# design.net
KiCad netlist of a schematic drawn in Altium Designer
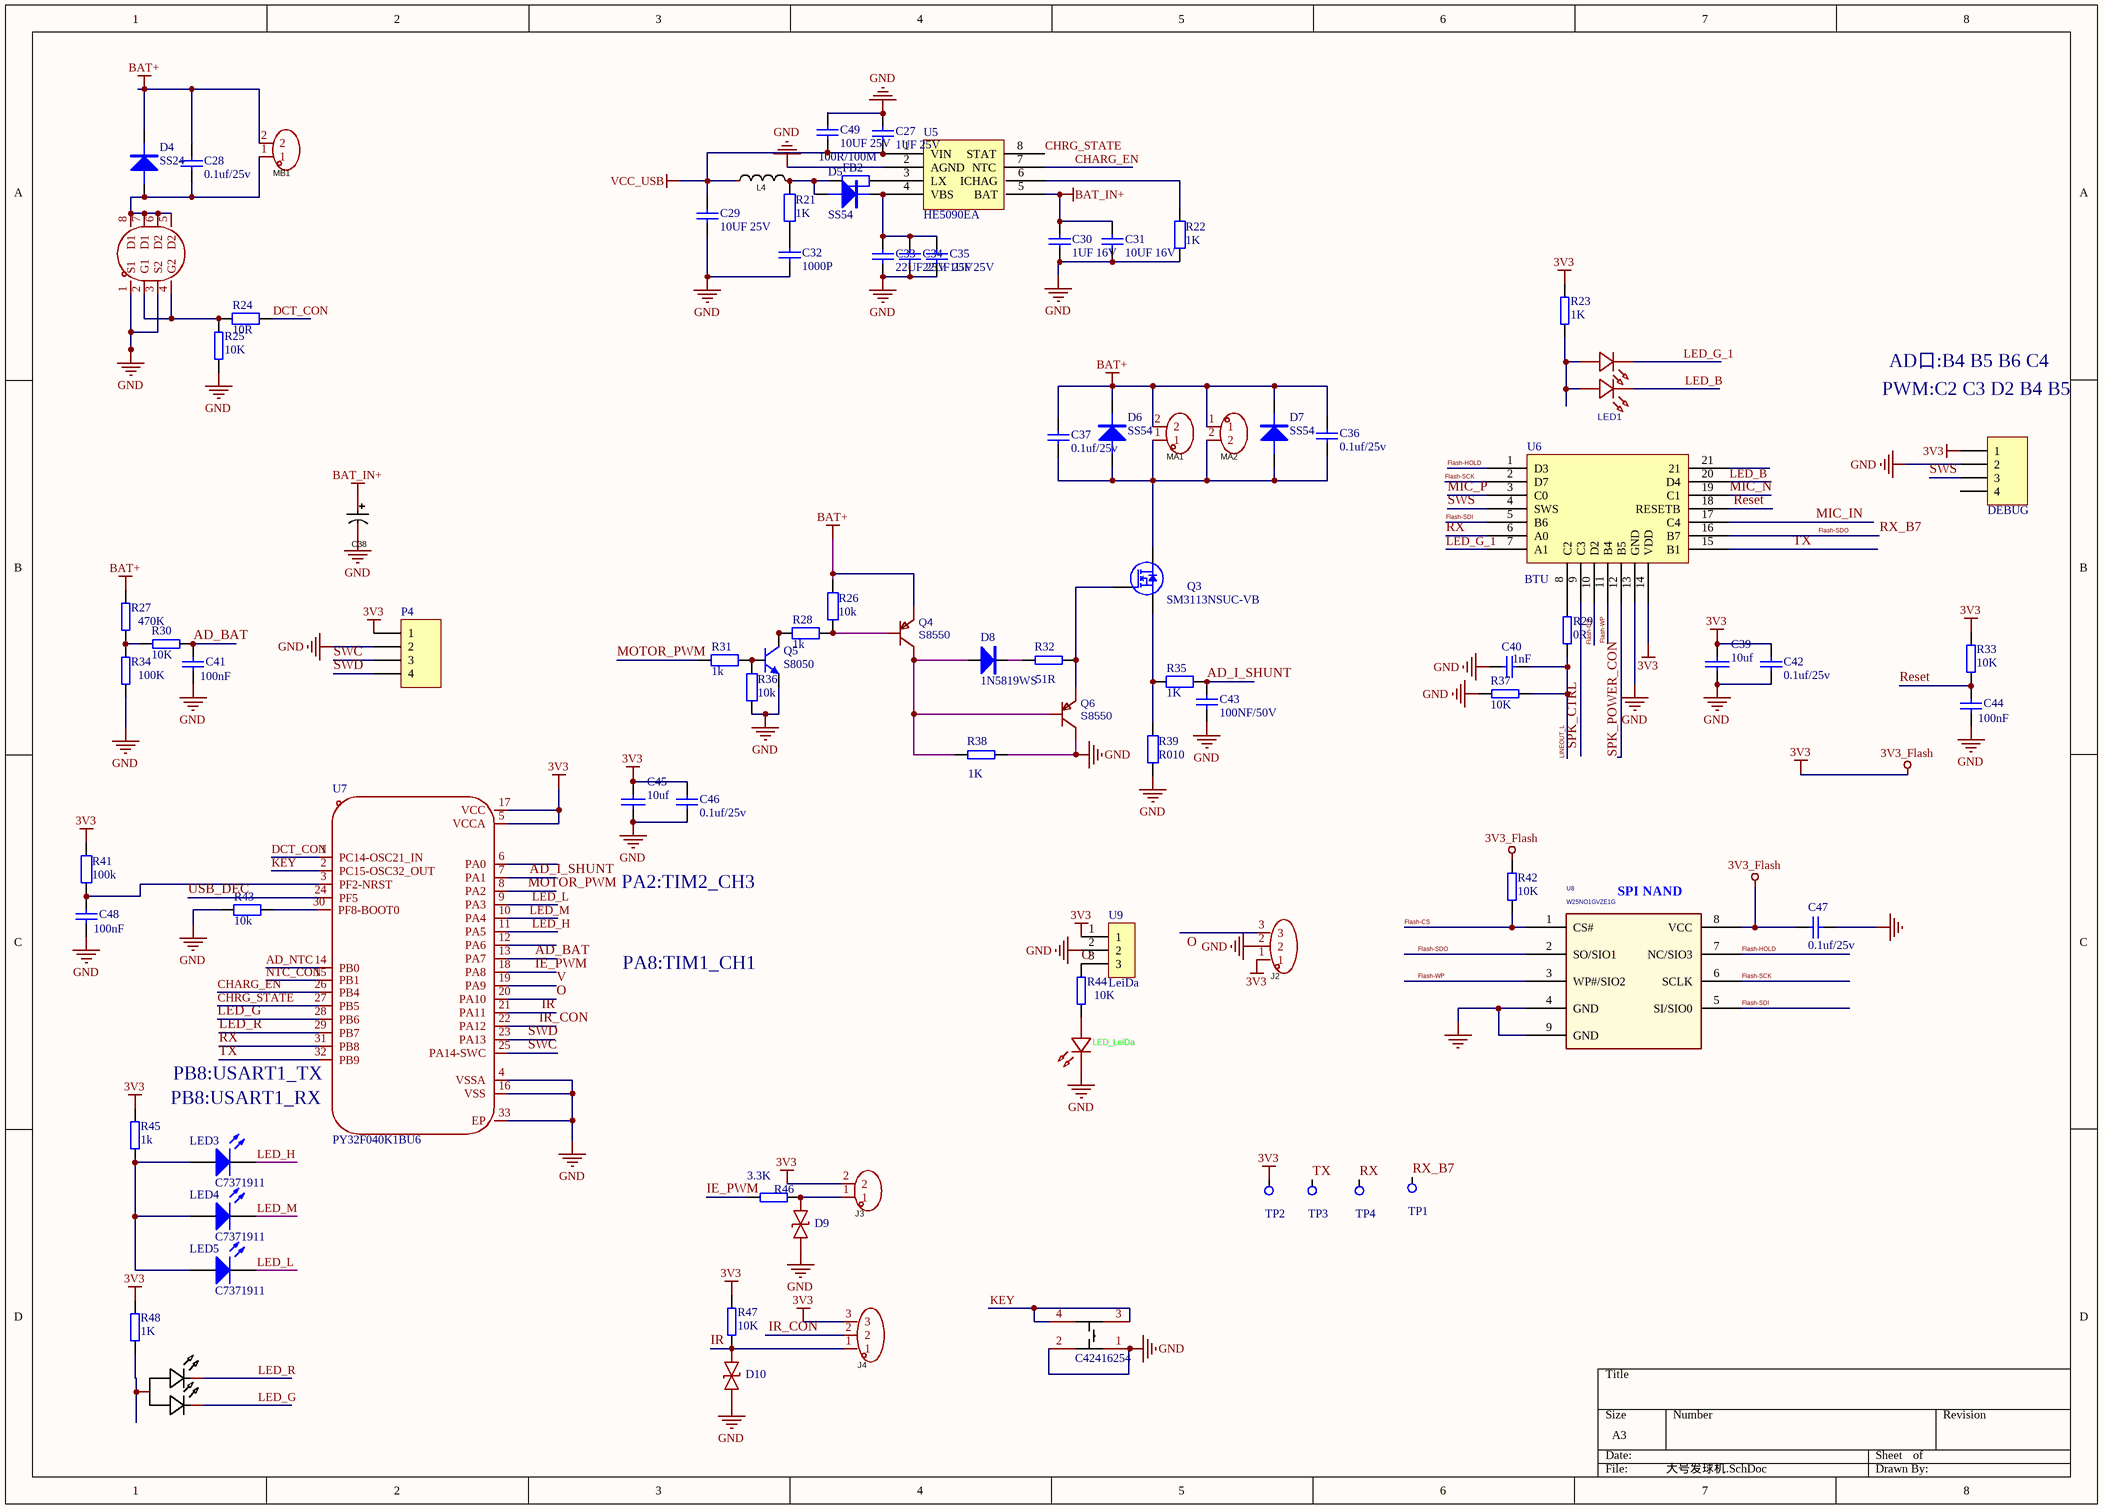
[diagram p0: 大号发球机.SchDoc]

(export (version "E")
  (design (tool "Eeschema 10.0.6"))
  (components
    (comp (ref "C27")
      (value "1UF 25V")
      (footprint "0603_C")
      (description "Capacitor")
      (fields (field (name "PUBLISHER") "Altium Limited"))
      (libsource (lib "*") (part "Cap"))
    )
    (comp (ref "C28")
      (value "0.1uf/25v")
      (footprint "0805_C")
      (description "Capacitor")
      (fields (field (name "PUBLISHER") "Altium Limited"))
      (libsource (lib "*") (part "Cap"))
    )
    (comp (ref "C29") (value "10UF 25V") (footprint "0603_c") (libsource (lib "DIY") (part "CAP")))
    (comp (ref "C30")
      (value "1UF 16V")
      (footprint "0603_C")
      (description "Capacitor")
      (fields (field (name "PUBLISHER") "Altium Limited"))
      (libsource (lib "*") (part "Cap"))
    )
    (comp (ref "C31") (value "10UF 16V") (footprint "0603_c") (libsource (lib "DIY") (part "CAP")))
    (comp (ref "C32")
      (value "1000P")
      (footprint "0603_C")
      (description "Capacitor")
      (fields (field (name "PUBLISHER") "Altium Limited"))
      (libsource (lib "*") (part "Cap"))
    )
    (comp (ref "C33") (value "22UF 25V") (footprint "0805_C") (libsource (lib "DIY") (part "CAP")))
    (comp (ref "C34") (value "22UF 25V") (footprint "0805_C") (libsource (lib "DIY") (part "CAP")))
    (comp (ref "C35")
      (value "1UF 25V")
      (footprint "0603_C")
      (description "Capacitor")
      (fields (field (name "PUBLISHER") "Altium Limited"))
      (libsource (lib "*") (part "Cap"))
    )
    (comp (ref "C36")
      (value "0.1uf/25v")
      (footprint "0805_C")
      (description "Capacitor")
      (fields (field (name "PUBLISHER") "Altium Limited"))
      (libsource (lib "*") (part "Cap"))
    )
    (comp (ref "C37")
      (value "0.1uf/25v")
      (footprint "0805_C")
      (description "Capacitor")
      (fields (field (name "PUBLISHER") "Altium Limited"))
      (libsource (lib "*") (part "Cap"))
    )
    (comp (ref "C38")
      (value "220uf/25v")
      (footprint "SMD 6.3*7.7")
      (fields (field (name "MANUFACTURER PART") "RVT1A221M0605"))
      (libsource (lib "altium-import") (part "root_0_RVT1A221M0605_C72494_"))
    )
    (comp (ref "C39")
      (value "10uf")
      (footprint "0603_c")
      (description "C-?-K-0603")
      (libsource (lib "HJ_AD_SchLib") (part "C-0603"))
    )
    (comp (ref "C40") (value "1nF") (footprint "0603_C") (libsource (lib "DIY") (part "CAP")))
    (comp (ref "C41") (value "100nF") (footprint "0603_C") (libsource (lib "DIY") (part "CAP")))
    (comp (ref "C42")
      (value "0.1uf/25v")
      (footprint "0603_C")
      (description "Capacitor")
      (fields (field (name "PUBLISHER") "Altium Limited"))
      (libsource (lib "*") (part "Cap"))
    )
    (comp (ref "C43")
      (value "100NF/50V")
      (footprint "0603_C")
      (description "无极电容")
      (libsource (lib "电容电阻电感保险") (part "Cap1"))
    )
    (comp (ref "C44") (value "100nF") (footprint "0603_C") (libsource (lib "DIY") (part "CAP")))
    (comp (ref "C45")
      (value "10uf")
      (footprint "0603_c")
      (description "C-?-K-0603")
      (libsource (lib "HJ_AD_SchLib") (part "C-0603"))
    )
    (comp (ref "C46")
      (value "0.1uf/25v")
      (footprint "0603_C")
      (description "Capacitor")
      (fields (field (name "PUBLISHER") "Altium Limited"))
      (libsource (lib "*") (part "Cap"))
    )
    (comp (ref "C47")
      (value "0.1uf/25v")
      (footprint "0603_C")
      (description "Capacitor")
      (fields (field (name "PUBLISHER") "Altium Limited"))
      (libsource (lib "*") (part "Cap"))
    )
    (comp (ref "C48") (value "100nF") (footprint "0603_C") (libsource (lib "DIY") (part "CAP")))
    (comp (ref "C49") (value "10UF 25V") (footprint "0603_c") (libsource (lib "DIY") (part "CAP")))
    (comp (ref "D4")
      (value "SS24")
      (footprint "SMA")
      (description "DO214AC")
      (libsource (lib "RONCO_SchLib") (part "D-SS24-SMA"))
    )
    (comp (ref "D5")
      (value "SS54")
      (footprint "SMA")
      (description "DO214AC")
      (libsource (lib "RONCO_SchLib") (part "D-SS24-SMA"))
    )
    (comp (ref "D6")
      (value "SS54")
      (footprint "SMA")
      (description "DO214AC")
      (libsource (lib "RONCO_SchLib") (part "D-SS24-SMA"))
    )
    (comp (ref "D7")
      (value "SS54")
      (footprint "SMA")
      (description "DO214AC")
      (libsource (lib "RONCO_SchLib") (part "D-SS24-SMA"))
    )
    (comp (ref "D8") (value "1N5819WS") (footprint "SOD-323") (libsource (lib "DIY") (part "DIODE")))
    (comp (ref "D9")
      (value "LESD5Z5.0CT1G")
      (footprint "SOD-523_L1.2-W0.8-LS1.6-RD")
      (libsource (lib "altium-import") (part "root_1_LESD5Z5.0CT1G_"))
    )
    (comp (ref "D10")
      (value "LESD5Z5.0CT1G")
      (footprint "SOD-523_L1.2-W0.8-LS1.6-RD")
      (libsource (lib "altium-import") (part "root_1_LESD5Z5.0CT1G_"))
    )
    (comp (ref "FB2")
      (value "100R/100M")
      (footprint "0805_R")
      (description "Resistor")
      (fields (field (name "PUBLISHER") "Altium Limited"))
      (libsource (lib "") (part "Res2_1"))
    )
    (comp (ref "J2")
      (value "2.0-3P LT")
      (footprint "CONN-SMD_2.0-3PLT")
      (fields (field (name "MANUFACTURER PART") "BX-PH2.0-3PZZ"))
      (libsource (lib "altium-import") (part "root_2_mirrored_BX-PH2.0-3PZZ_"))
    )
    (comp (ref "J3")
      (value "2.54-2P LT")
      (footprint "CONN-SMD_2.54-2PLT")
      (fields (field (name "MANUFACTURER PART") "BX-PH2.0-2PZZ"))
      (libsource (lib "altium-import") (part "root_2_mirrored_BX-PH2.0-2PZZ_"))
    )
    (comp (ref "J4")
      (value "2.54-3P LT")
      (footprint "CONN-SMD_2.54-3P-LT")
      (fields (field (name "MANUFACTURER PART") "BX-PH2.0-3PZZ"))
      (libsource (lib "altium-import") (part "root_2_mirrored_BX-PH2.0-3PZZ_"))
    )
    (comp (ref "K1")
      (value "C42416254")
      (footprint "KEY_SMD_4P")
      (fields (field (name "MANUFACTURER PART") "TS-1002S-05026C"))
      (libsource (lib "altium-import") (part "root_2_TS-1002S-05026C_"))
    )
    (comp (ref "L4")
      (value "0630-2R2")
      (footprint "L 6.6*7.0")
      (fields (field (name "MANUFACTURER PART") "FXL0630-4R7-M"))
      (libsource (lib "altium-import") (part "root_0_FXL0630-4R7-M_"))
    )
    (comp (ref "LED1")
      (value "bl-hb5gk33b-trb")
      (footprint "LED-SMD_4P-L3.2-W2.7-P1.40-TL_BL-HB5GK33B-TRB")
      (fields (field (name "MANUFACTURERPART") "BL-HB5GK33B-TRB"))
      (libsource (lib "altium-import") (part "root_2_bl-hb5gk33b-trb_"))
    )
    (comp (ref "LED2")
      (value "LED_LeiDa")
      (footprint "0805_LED")
      (fields (field (name "MANUFACTURER PART") "XL-2012SURC"))
      (libsource (lib "altium-import") (part "root_1_XL-2012SURC_"))
    )
    (comp (ref "LED3")
      (value "C7371911")
      (footprint "0805_LED")
      (description "Typical INFRARED GaAs LED")
      (fields (field (name "PUBLISHER") "Altium Limited"))
      (libsource (lib "Miscellaneous Devices") (part "LED0"))
    )
    (comp (ref "LED4")
      (value "C7371911")
      (footprint "0805_LED")
      (description "Typical INFRARED GaAs LED")
      (fields (field (name "PUBLISHER") "Altium Limited"))
      (libsource (lib "Miscellaneous Devices") (part "LED0"))
    )
    (comp (ref "LED5")
      (value "C7371911")
      (footprint "0805_LED")
      (description "Typical INFRARED GaAs LED")
      (fields (field (name "PUBLISHER") "Altium Limited"))
      (libsource (lib "Miscellaneous Devices") (part "LED0"))
    )
    (comp (ref "LED6")
      (value "C5221230")
      (footprint "LED-SMD_4P-L3.2-W1.6-TL_XL-3216SURUGC")
      (fields (field (name "MANUFACTURER PART") "TZ-LAMP03RG4HD-A"))
      (libsource (lib "altium-import") (part "root_0_TZ-LAMP03RG4HD-A_"))
    )
    (comp (ref "MA1")
      (value "2.54-2P LT")
      (footprint "CONN-SMD_2.54-2PLT")
      (fields (field (name "MANUFACTURER PART") "BX-PH2.0-2PZZ"))
      (libsource (lib "altium-import") (part "root_2_mirrored_BX-PH2.0-2PZZ_"))
    )
    (comp (ref "MA2")
      (value "2.54-2P LT")
      (footprint "CONN-SMD_2.54-2PLT")
      (fields (field (name "MANUFACTURER PART") "BX-PH2.0-2PZZ"))
      (libsource (lib "altium-import") (part "root_0_BX-PH2.0-2PZZ_"))
    )
    (comp (ref "MB1")
      (value "2.54-2P LT")
      (footprint "CONN-SMD_2.54-2PLT")
      (fields (field (name "MANUFACTURER PART") "BX-PH2.0-2PZZ"))
      (libsource (lib "altium-import") (part "root_2_mirrored_BX-PH2.0-2PZZ_"))
    )
    (comp (ref "P3")
      (value "DEBUG")
      (footprint "SIP4-2.54")
      (description "Header, 4-Pin")
      (fields (field (name "PUBLISHER") "Altium Limited"))
      (libsource (lib "Miscellaneous Connectors") (part "Header 4"))
    )
    (comp (ref "P4")
      (value "~")
      (footprint "4P 2.0")
      (description "Header, 4-Pin")
      (fields (field (name "PUBLISHER") "Altium Limited"))
      (libsource (lib "Miscellaneous Connectors") (part "Header 4"))
    )
    (comp (ref "Q2")
      (value "AP9926")
      (footprint "SOP8")
      (fields (field (name "MANUFACTURER") "WINSOK(微硕)") (field (name "MANUFACTURER PART") "WSP9936"))
      (libsource (lib "altium-import") (part "root_1_WSP9936_"))
    )
    (comp (ref "Q3")
      (value "SM3113NSUC-VB")
      (footprint "TO-252")
      (description "N沟道MOS管")
      (libsource (lib "二三极管mos可控硅") (part "NMOS1"))
    )
    (comp (ref "Q4")
      (value "S8550")
      (footprint "SOT-23")
      (fields (field (name "BOM_SUPPLIER PART") "C545533") (field (name "CONTRIBUTOR") "LCSC"))
      (libsource (lib "altium-import") (part "root_2_mirrored_S8550_C545533_"))
    )
    (comp (ref "Q5")
      (value "S8050")
      (footprint "SOT-23(SOT-23-3)")
      (description "NPN三极管")
      (libsource (lib "二三极管mos可控硅") (part "NPN_sot23"))
    )
    (comp (ref "Q6")
      (value "S8550")
      (footprint "SOT-23")
      (fields (field (name "BOM_SUPPLIER PART") "C545533") (field (name "CONTRIBUTOR") "LCSC"))
      (libsource (lib "altium-import") (part "root_2_mirrored_S8550_C545533_"))
    )
    (comp (ref "R21")
      (value "1K")
      (footprint "0603_R")
      (description "Resistor")
      (fields (field (name "PUBLISHER") "Altium Limited"))
      (libsource (lib "") (part "Res2_2"))
    )
    (comp (ref "R22")
      (value "1K")
      (footprint "0603_R")
      (description "Resistor")
      (fields (field (name "PUBLISHER") "Altium Limited"))
      (libsource (lib "") (part "Res2_2"))
    )
    (comp (ref "R23") (value "1K") (footprint "0603_R") (libsource (lib "DIY") (part "RES")))
    (comp (ref "R24")
      (value "10R")
      (footprint "0603_R")
      (description "Resistor")
      (fields (field (name "PUBLISHER") "Altium Limited"))
      (libsource (lib "") (part "Res2_1"))
    )
    (comp (ref "R25") (value "10K") (footprint "0603_R") (libsource (lib "DIY") (part "RES")))
    (comp (ref "R26")
      (value "10k")
      (footprint "0603_R")
      (description "Resistor")
      (fields (field (name "PUBLISHER") "Altium Limited"))
      (libsource (lib "*") (part "Res2"))
    )
    (comp (ref "R27") (value "470K") (footprint "0603_R") (libsource (lib "DIY") (part "RES")))
    (comp (ref "R28")
      (value "1k")
      (footprint "0603_R")
      (description "Resistor")
      (fields (field (name "PUBLISHER") "Altium Limited"))
      (libsource (lib "") (part "Res2_3"))
    )
    (comp (ref "R29") (value "0R") (footprint "0603_R") (libsource (lib "DIY") (part "RES")))
    (comp (ref "R30") (value "10K") (footprint "0603_R") (libsource (lib "DIY") (part "RES")))
    (comp (ref "R31")
      (value "1k")
      (footprint "0603_R")
      (description "Resistor")
      (fields (field (name "PUBLISHER") "Altium Limited"))
      (libsource (lib "") (part "Res2_3"))
    )
    (comp (ref "R32") (value "51R") (footprint "0603_R") (libsource (lib "*") (part "RES")))
    (comp (ref "R33") (value "10K") (footprint "0603_R") (libsource (lib "DIY") (part "RES")))
    (comp (ref "R34") (value "100K") (footprint "0603_R") (libsource (lib "DIY") (part "RES")))
    (comp (ref "R35")
      (value "1K")
      (footprint "0603_R")
      (description "Resistor")
      (fields (field (name "PUBLISHER") "Altium Limited"))
      (libsource (lib "") (part "Res2_1"))
    )
    (comp (ref "R36")
      (value "10k")
      (footprint "0603_R")
      (description "Resistor")
      (fields (field (name "PUBLISHER") "Altium Limited"))
      (libsource (lib "*") (part "Res2"))
    )
    (comp (ref "R37") (value "10K") (footprint "0603_R") (libsource (lib "DIY") (part "RES")))
    (comp (ref "R38") (value "1K") (footprint "0603_R") (libsource (lib "*") (part "RES")))
    (comp (ref "R39")
      (value "R010")
      (footprint "2512_R")
      (description "Resistor")
      (fields (field (name "PUBLISHER") "Altium Limited"))
      (libsource (lib "*") (part "Res2"))
    )
    (comp (ref "R41")
      (value "100k")
      (footprint "0603_R")
      (description "Resistor")
      (fields (field (name "PUBLISHER") "Altium Limited"))
      (libsource (lib "") (part "Res2_2"))
    )
    (comp (ref "R42") (value "10K") (footprint "0603_R") (libsource (lib "DIY") (part "RES")))
    (comp (ref "R43")
      (value "10k")
      (footprint "0603_R")
      (description "Resistor")
      (fields (field (name "PUBLISHER") "Altium Limited"))
      (libsource (lib "") (part "Res2_1"))
    )
    (comp (ref "R44") (value "10K") (footprint "0603_R") (libsource (lib "DIY") (part "RES")))
    (comp (ref "R45") (value "1k") (footprint "0603_r") (libsource (lib "DIY") (part "RES")))
    (comp (ref "R46") (value "3.3K") (footprint "0603_R") (libsource (lib "DIY") (part "RES")))
    (comp (ref "R47") (value "10K") (footprint "0603_R") (libsource (lib "DIY") (part "RES")))
    (comp (ref "R48") (value "1K") (footprint "0603_R") (libsource (lib "DIY") (part "RES")))
    (comp (ref "TP1") (value "~") (footprint "TP") (libsource (lib "LZJ自用") (part "J-CSD")))
    (comp (ref "TP2") (value "~") (footprint "TP") (libsource (lib "LZJ自用") (part "J-CSD")))
    (comp (ref "TP3") (value "~") (footprint "TP") (libsource (lib "LZJ自用") (part "J-CSD")))
    (comp (ref "TP4") (value "~") (footprint "TP") (libsource (lib "LZJ自用") (part "J-CSD")))
    (comp (ref "U5") (value "HE5090EA") (footprint "SOP8-9") (libsource (lib "MyLib") (part "HE5090EA")))
    (comp (ref "U6") (value "BTU") (footprint "BTU") (libsource (lib "MyLib") (part "BTU")))
    (comp (ref "U7")
      (value "PY32F040K1BU6")
      (footprint "QFN-32_L5.0-W5.0-P0.50-BL-EP3.4")
      (libsource (lib "MyLib") (part "PY32F040K1BU6"))
    )
    (comp (ref "U8") (value "W25NO1GVZE1G") (footprint "SOP8-150+208") (libsource (lib "*") (part "24C08_3")))
    (comp (ref "U9") (value "LeiDa") (footprint "5.8G") (libsource (lib "MyLib") (part "CON3")))
  )
  (nets
    (net (code "1") (name "/AD_BAT") (class "Default")
      (node (ref "C41") (pin "2") (pintype "passive"))
      (node (ref "R30") (pin "2") (pinfunction "2_2") (pintype "passive"))
      (node (ref "U7") (pin "13") (pinfunction "PA7_13") (pintype "passive"))
    )
    (net (code "2") (name "/AD_I_SHUNT") (class "Default")
      (node (ref "C43") (pin "1") (pinfunction "1_1") (pintype "passive"))
      (node (ref "R35") (pin "1") (pinfunction "1_1") (pintype "passive"))
      (node (ref "U7") (pin "7") (pinfunction "PA1_7") (pintype "passive"))
    )
    (net (code "3") (name "/AD_NTC") (class "Default")
      (node (ref "U7") (pin "14") (pinfunction "PB0_14") (pintype "passive"))
    )
    (net (code "4") (name "/CHARG_EN") (class "Default")
      (node (ref "U5") (pin "7") (pinfunction "NTC_7") (pintype "passive"))
      (node (ref "U7") (pin "26") (pinfunction "PB4_26") (pintype "passive"))
    )
    (net (code "5") (name "/CHRG_STATE") (class "Default")
      (node (ref "U5") (pin "8") (pinfunction "STAT_8") (pintype "passive"))
      (node (ref "U7") (pin "27") (pinfunction "PB5_27") (pintype "passive"))
    )
    (net (code "6") (name "/DCT_CON") (class "Default")
      (node (ref "R24") (pin "1") (pinfunction "1_1") (pintype "passive"))
      (node (ref "U7") (pin "1") (pinfunction "PC14-OSC21_IN_1") (pintype "passive"))
    )
    (net (code "7") (name "/Flash-CS") (class "Default")
      (node (ref "R42") (pin "1") (pinfunction "1_1") (pintype "passive"))
      (node (ref "U6") (pin "10") (pinfunction "D2_10") (pintype "passive"))
      (node (ref "U8") (pin "1") (pinfunction "CS#_1") (pintype "passive"))
    )
    (net (code "8") (name "/Flash-HOLD") (class "Default")
      (node (ref "U6") (pin "1") (pinfunction "D3_1") (pintype "passive"))
      (node (ref "U8") (pin "7") (pinfunction "NC/SIO3_7") (pintype "passive"))
    )
    (net (code "9") (name "/Flash-SCK") (class "Default")
      (node (ref "U6") (pin "2") (pinfunction "D7_2") (pintype "passive"))
      (node (ref "U8") (pin "6") (pinfunction "SCLK_6") (pintype "passive"))
    )
    (net (code "10") (name "/Flash-SDI") (class "Default")
      (node (ref "U6") (pin "5") (pinfunction "B6_5") (pintype "passive"))
      (node (ref "U8") (pin "5") (pinfunction "SI/SIO0_5") (pintype "passive"))
    )
    (net (code "11") (name "/Flash-SDO") (class "Default")
      (node (ref "TP1") (pin "1") (pinfunction "1_1") (pintype "passive"))
      (node (ref "U6") (pin "16") (pinfunction "B7_16") (pintype "passive"))
      (node (ref "U8") (pin "2") (pinfunction "SO/SIO1_2") (pintype "passive"))
    )
    (net (code "12") (name "/Flash-WP") (class "Default")
      (node (ref "U6") (pin "11") (pinfunction "B4_11") (pintype "passive"))
      (node (ref "U8") (pin "3") (pinfunction "WP#/SIO2_3") (pintype "passive"))
    )
    (net (code "13") (name "/IE_PWM") (class "Default")
      (node (ref "R46") (pin "1") (pinfunction "1_1") (pintype "passive"))
      (node (ref "U7") (pin "18") (pinfunction "PA8_18") (pintype "passive"))
    )
    (net (code "14") (name "/IR") (class "Default")
      (node (ref "D10") (pin "2") (pinfunction "2_2") (pintype "passive"))
      (node (ref "J4") (pin "1") (pinfunction "1_1") (pintype "passive"))
      (node (ref "R47") (pin "1") (pinfunction "1_1") (pintype "passive"))
      (node (ref "U7") (pin "21") (pinfunction "PA11_21") (pintype "passive"))
    )
    (net (code "15") (name "/IR_CON") (class "Default")
      (node (ref "J4") (pin "2") (pinfunction "2_2") (pintype "passive"))
      (node (ref "U7") (pin "22") (pinfunction "PA12_22") (pintype "passive"))
    )
    (net (code "16") (name "/KEY") (class "Default")
      (node (ref "K1") (pin "3") (pinfunction "3_3") (pintype "passive"))
      (node (ref "K1") (pin "4") (pinfunction "4_4") (pintype "passive"))
      (node (ref "U7") (pin "2") (pinfunction "PC15-OSC32_OUT_2") (pintype "passive"))
    )
    (net (code "17") (name "/LED_B") (class "Default")
      (node (ref "LED1") (pin "1") (pinfunction "C_1") (pintype "passive"))
      (node (ref "U6") (pin "20") (pinfunction "D4_20") (pintype "passive"))
    )
    (net (code "18") (name "/LED_G") (class "Default")
      (node (ref "LED6") (pin "3") (pinfunction "-_3") (pintype "passive"))
      (node (ref "U7") (pin "28") (pinfunction "PB6_28") (pintype "passive"))
    )
    (net (code "19") (name "/LED_G_1") (class "Default")
      (node (ref "LED1") (pin "2") (pinfunction "C_2") (pintype "passive"))
      (node (ref "U6") (pin "7") (pinfunction "A1_7") (pintype "passive"))
    )
    (net (code "20") (name "/LED_H") (class "Default")
      (node (ref "LED3") (pin "2") (pinfunction "K_2") (pintype "passive"))
      (node (ref "U7") (pin "11") (pinfunction "PA5_11") (pintype "passive"))
    )
    (net (code "21") (name "/LED_L") (class "Default")
      (node (ref "LED5") (pin "2") (pinfunction "K_2") (pintype "passive"))
      (node (ref "U7") (pin "9") (pinfunction "PA3_9") (pintype "passive"))
    )
    (net (code "22") (name "/LED_M") (class "Default")
      (node (ref "LED4") (pin "2") (pinfunction "K_2") (pintype "passive"))
      (node (ref "U7") (pin "10") (pinfunction "PA4_10") (pintype "passive"))
    )
    (net (code "23") (name "/LED_R") (class "Default")
      (node (ref "LED6") (pin "1") (pinfunction "-_1") (pintype "passive"))
      (node (ref "U7") (pin "29") (pinfunction "PB7_29") (pintype "passive"))
    )
    (net (code "24") (name "/LINEOUT_L") (class "Default")
      (node (ref "C40") (pin "1") (pintype "passive"))
      (node (ref "R29") (pin "1") (pinfunction "1_1") (pintype "passive"))
      (node (ref "R37") (pin "2") (pinfunction "2_2") (pintype "passive"))
    )
    (net (code "25") (name "/MIC_IN") (class "Default")
      (node (ref "U6") (pin "17") (pinfunction "C4_17") (pintype "passive"))
    )
    (net (code "26") (name "/MIC_N") (class "Default")
      (node (ref "U6") (pin "19") (pinfunction "C1_19") (pintype "passive"))
    )
    (net (code "27") (name "/MIC_P") (class "Default")
      (node (ref "U6") (pin "3") (pinfunction "C0_3") (pintype "passive"))
    )
    (net (code "28") (name "/MOTOR_PWM") (class "Default")
      (node (ref "R31") (pin "1") (pinfunction "1_1") (pintype "passive"))
      (node (ref "U7") (pin "8") (pinfunction "PA2_8") (pintype "passive"))
    )
    (net (code "29") (name "/NTC_CON") (class "Default")
      (node (ref "U7") (pin "15") (pinfunction "PB1_15") (pintype "passive"))
    )
    (net (code "30") (name "/O") (class "Default")
      (node (ref "J2") (pin "3") (pinfunction "3_3") (pintype "passive"))
      (node (ref "R44") (pin "1") (pinfunction "1_1") (pintype "passive"))
      (node (ref "U7") (pin "20") (pinfunction "PA10_20") (pintype "passive"))
      (node (ref "U9") (pin "3") (pinfunction "3_3") (pintype "passive"))
    )
    (net (code "31") (name "/RX") (class "Default")
      (node (ref "TP4") (pin "1") (pinfunction "1_1") (pintype "passive"))
      (node (ref "U6") (pin "6") (pinfunction "A0_6") (pintype "passive"))
      (node (ref "U7") (pin "31") (pinfunction "PB8_31") (pintype "passive"))
    )
    (net (code "32") (name "/Reset") (class "Default")
      (node (ref "C44") (pin "2") (pintype "passive"))
      (node (ref "R33") (pin "2") (pinfunction "2_2") (pintype "passive"))
      (node (ref "U6") (pin "18") (pinfunction "RESETB_18") (pintype "passive"))
    )
    (net (code "33") (name "/SPK_CTRL") (class "Default")
      (node (ref "U6") (pin "9") (pinfunction "C3_9") (pintype "passive"))
    )
    (net (code "34") (name "/SPK_POWER_CON") (class "Default")
      (node (ref "U6") (pin "12") (pinfunction "B5_12") (pintype "passive"))
    )
    (net (code "35") (name "/SWC") (class "Default")
      (node (ref "P4") (pin "3") (pinfunction "3_3") (pintype "passive"))
      (node (ref "U7") (pin "25") (pinfunction "PA14-SWC_25") (pintype "passive"))
    )
    (net (code "36") (name "/SWD") (class "Default")
      (node (ref "P4") (pin "4") (pinfunction "4_4") (pintype "passive"))
      (node (ref "U7") (pin "23") (pinfunction "PA13_23") (pintype "passive"))
    )
    (net (code "37") (name "/SWS") (class "Default")
      (node (ref "P3") (pin "3") (pinfunction "3_3") (pintype "passive"))
      (node (ref "U6") (pin "4") (pinfunction "SWS_4") (pintype "passive"))
    )
    (net (code "38") (name "/TX") (class "Default")
      (node (ref "TP3") (pin "1") (pinfunction "1_1") (pintype "passive"))
      (node (ref "U6") (pin "15") (pinfunction "B1_15") (pintype "passive"))
      (node (ref "U7") (pin "32") (pinfunction "PB9_32") (pintype "passive"))
    )
    (net (code "39") (name "/USB_DEC") (class "Default")
      (node (ref "U7") (pin "24") (pinfunction "PF5_24") (pintype "passive"))
    )
    (net (code "40") (name "/V") (class "Default")
      (node (ref "U7") (pin "19") (pinfunction "PA9_19") (pintype "passive"))
    )
    (net (code "41") (name "3V3") (class "Default")
      (node (ref "C39") (pin "2") (pinfunction "2_2") (pintype "passive"))
      (node (ref "C42") (pin "1") (pinfunction "1_1") (pintype "passive"))
      (node (ref "C45") (pin "2") (pinfunction "2_2") (pintype "passive"))
      (node (ref "C46") (pin "1") (pinfunction "1_1") (pintype "passive"))
      (node (ref "C47") (pin "1") (pinfunction "1_1") (pintype "passive"))
      (node (ref "J2") (pin "1") (pinfunction "1_1") (pintype "passive"))
      (node (ref "J3") (pin "2") (pinfunction "2_2") (pintype "passive"))
      (node (ref "J4") (pin "3") (pinfunction "3_3") (pintype "passive"))
      (node (ref "P3") (pin "1") (pinfunction "1_1") (pintype "passive"))
      (node (ref "P4") (pin "1") (pinfunction "1_1") (pintype "passive"))
      (node (ref "R23") (pin "1") (pinfunction "1_1") (pintype "passive"))
      (node (ref "R33") (pin "1") (pinfunction "1_1") (pintype "passive"))
      (node (ref "R41") (pin "1") (pinfunction "1_1") (pintype "passive"))
      (node (ref "R42") (pin "2") (pinfunction "2_2") (pintype "passive"))
      (node (ref "R45") (pin "1") (pinfunction "1_1") (pintype "passive"))
      (node (ref "R47") (pin "2") (pinfunction "2_2") (pintype "passive"))
      (node (ref "R48") (pin "1") (pinfunction "1_1") (pintype "passive"))
      (node (ref "TP2") (pin "1") (pinfunction "1_1") (pintype "passive"))
      (node (ref "U6") (pin "14") (pinfunction "VDD_14") (pintype "passive"))
      (node (ref "U7") (pin "17") (pinfunction "VCC_17") (pintype "passive"))
      (node (ref "U7") (pin "5") (pinfunction "VCCA_5") (pintype "passive"))
      (node (ref "U8") (pin "8") (pinfunction "VCC_8") (pintype "passive"))
      (node (ref "U9") (pin "1") (pinfunction "1_1") (pintype "passive"))
    )
    (net (code "42") (name "BAT+") (class "Default")
      (node (ref "C28") (pin "2") (pinfunction "2_2") (pintype "passive"))
      (node (ref "C36") (pin "2") (pinfunction "2_2") (pintype "passive"))
      (node (ref "C37") (pin "2") (pinfunction "2_2") (pintype "passive"))
      (node (ref "D4") (pin "2") (pinfunction "K_2") (pintype "passive"))
      (node (ref "D6") (pin "2") (pinfunction "K_2") (pintype "passive"))
      (node (ref "D7") (pin "2") (pinfunction "K_2") (pintype "passive"))
      (node (ref "MA1") (pin "2") (pinfunction "2_2") (pintype "passive"))
      (node (ref "MA2") (pin "1") (pinfunction "1_1") (pintype "passive"))
      (node (ref "MB1") (pin "2") (pinfunction "2_2") (pintype "passive"))
      (node (ref "Q4") (pin "2") (pinfunction "E_2") (pintype "passive"))
      (node (ref "R26") (pin "2") (pinfunction "2_2") (pintype "passive"))
      (node (ref "R27") (pin "1") (pinfunction "1_1") (pintype "passive"))
    )
    (net (code "43") (name "BAT_IN+") (class "Default")
      (node (ref "C30") (pin "2") (pinfunction "2_2") (pintype "passive"))
      (node (ref "C31") (pin "1") (pintype "passive"))
      (node (ref "C38") (pin "1") (pinfunction "1_1") (pintype "passive"))
      (node (ref "U5") (pin "5") (pinfunction "BAT_5") (pintype "passive"))
    )
    (net (code "44") (name "GND") (class "Default")
      (node (ref "C27") (pin "2") (pinfunction "2_2") (pintype "passive"))
      (node (ref "C29") (pin "2") (pintype "passive"))
      (node (ref "C30") (pin "1") (pinfunction "1_1") (pintype "passive"))
      (node (ref "C31") (pin "2") (pintype "passive"))
      (node (ref "C32") (pin "1") (pinfunction "1_1") (pintype "passive"))
      (node (ref "C33") (pin "1") (pintype "passive"))
      (node (ref "C34") (pin "1") (pintype "passive"))
      (node (ref "C35") (pin "1") (pinfunction "1_1") (pintype "passive"))
      (node (ref "C38") (pin "2") (pinfunction "2_2") (pintype "passive"))
      (node (ref "C39") (pin "1") (pinfunction "1_1") (pintype "passive"))
      (node (ref "C40") (pin "2") (pintype "passive"))
      (node (ref "C41") (pin "1") (pintype "passive"))
      (node (ref "C42") (pin "2") (pinfunction "2_2") (pintype "passive"))
      (node (ref "C43") (pin "2") (pinfunction "2_2") (pintype "passive"))
      (node (ref "C44") (pin "1") (pintype "passive"))
      (node (ref "C45") (pin "1") (pinfunction "1_1") (pintype "passive"))
      (node (ref "C46") (pin "2") (pinfunction "2_2") (pintype "passive"))
      (node (ref "C47") (pin "2") (pinfunction "2_2") (pintype "passive"))
      (node (ref "C48") (pin "1") (pintype "passive"))
      (node (ref "C49") (pin "1") (pintype "passive"))
      (node (ref "D10") (pin "1") (pinfunction "1_1") (pintype "passive"))
      (node (ref "D9") (pin "1") (pinfunction "1_1") (pintype "passive"))
      (node (ref "J2") (pin "2") (pinfunction "2_2") (pintype "passive"))
      (node (ref "K1") (pin "1") (pinfunction "1_1") (pintype "passive"))
      (node (ref "K1") (pin "2") (pinfunction "2_2") (pintype "passive"))
      (node (ref "LED2") (pin "2") (pinfunction "K_2") (pintype "passive"))
      (node (ref "P3") (pin "2") (pinfunction "2_2") (pintype "passive"))
      (node (ref "P4") (pin "2") (pinfunction "2_2") (pintype "passive"))
      (node (ref "Q2") (pin "1") (pinfunction "S1_1") (pintype "passive"))
      (node (ref "Q2") (pin "3") (pinfunction "S2_3") (pintype "passive"))
      (node (ref "Q5") (pin "2") (pinfunction "E_2") (pintype "passive"))
      (node (ref "Q6") (pin "3") (pinfunction "C_3") (pintype "passive"))
      (node (ref "R22") (pin "2") (pinfunction "2_2") (pintype "passive"))
      (node (ref "R25") (pin "1") (pinfunction "1_1") (pintype "passive"))
      (node (ref "R34") (pin "2") (pinfunction "2_2") (pintype "passive"))
      (node (ref "R36") (pin "1") (pinfunction "1_1") (pintype "passive"))
      (node (ref "R37") (pin "1") (pinfunction "1_1") (pintype "passive"))
      (node (ref "R38") (pin "1") (pintype "passive"))
      (node (ref "R39") (pin "1") (pinfunction "1_1") (pintype "passive"))
      (node (ref "R43") (pin "2") (pinfunction "2_2") (pintype "passive"))
      (node (ref "U5") (pin "2") (pinfunction "AGND_2") (pintype "passive"))
      (node (ref "U6") (pin "13") (pinfunction "GND_13") (pintype "passive"))
      (node (ref "U7") (pin "16") (pinfunction "VSS_16") (pintype "passive"))
      (node (ref "U7") (pin "33") (pinfunction "EP_33") (pintype "passive"))
      (node (ref "U7") (pin "4") (pinfunction "VSSA_4") (pintype "passive"))
      (node (ref "U8") (pin "4") (pinfunction "GND_4") (pintype "passive"))
      (node (ref "U8") (pin "9") (pinfunction "GND_9") (pintype "passive"))
      (node (ref "U9") (pin "2") (pinfunction "2_2") (pintype "passive"))
    )
    (net (code "45") (name "Net-(C32-Pad2)") (class "Default")
      (node (ref "C32") (pin "2") (pinfunction "2_2") (pintype "passive"))
      (node (ref "R21") (pin "2") (pinfunction "2_2") (pintype "passive"))
    )
    (net (code "46") (name "Net-(D4-A)") (class "Default")
      (node (ref "C28") (pin "1") (pinfunction "1_1") (pintype "passive"))
      (node (ref "D4") (pin "1") (pinfunction "A_1") (pintype "passive"))
      (node (ref "MB1") (pin "1") (pinfunction "1_1") (pintype "passive"))
      (node (ref "Q2") (pin "5") (pinfunction "D2_5") (pintype "passive"))
      (node (ref "Q2") (pin "6") (pinfunction "D2_6") (pintype "passive"))
      (node (ref "Q2") (pin "7") (pinfunction "D1_7") (pintype "passive"))
      (node (ref "Q2") (pin "8") (pinfunction "D1_8") (pintype "passive"))
    )
    (net (code "47") (name "Net-(D5-A)") (class "Default")
      (node (ref "D5") (pin "1") (pinfunction "A_1") (pintype "passive"))
      (node (ref "FB2") (pin "2") (pinfunction "2_2") (pintype "passive"))
      (node (ref "L4") (pin "2") (pinfunction "2_2") (pintype "passive"))
      (node (ref "R21") (pin "1") (pinfunction "1_1") (pintype "passive"))
    )
    (net (code "48") (name "Net-(D5-K)") (class "Default")
      (node (ref "C33") (pin "2") (pintype "passive"))
      (node (ref "C34") (pin "2") (pintype "passive"))
      (node (ref "C35") (pin "2") (pinfunction "2_2") (pintype "passive"))
      (node (ref "D5") (pin "2") (pinfunction "K_2") (pintype "passive"))
      (node (ref "U5") (pin "4") (pinfunction "VBS_4") (pintype "passive"))
    )
    (net (code "49") (name "Net-(D6-A)") (class "Default")
      (node (ref "C36") (pin "1") (pinfunction "1_1") (pintype "passive"))
      (node (ref "C37") (pin "1") (pinfunction "1_1") (pintype "passive"))
      (node (ref "D6") (pin "1") (pinfunction "A_1") (pintype "passive"))
      (node (ref "D7") (pin "1") (pinfunction "A_1") (pintype "passive"))
      (node (ref "MA1") (pin "1") (pinfunction "1_1") (pintype "passive"))
      (node (ref "MA2") (pin "2") (pinfunction "2_2") (pintype "passive"))
      (node (ref "Q3") (pin "2") (pinfunction "D_2") (pintype "passive"))
    )
    (net (code "50") (name "Net-(D8-A)") (class "Default")
      (node (ref "D8") (pin "1") (pinfunction "A_1") (pintype "passive"))
      (node (ref "Q4") (pin "3") (pinfunction "C_3") (pintype "passive"))
      (node (ref "Q6") (pin "1") (pinfunction "B_1") (pintype "passive"))
      (node (ref "R38") (pin "2") (pintype "passive"))
    )
    (net (code "51") (name "Net-(D8-K)") (class "Default")
      (node (ref "D8") (pin "2") (pinfunction "K_2") (pintype "passive"))
      (node (ref "R32") (pin "2") (pintype "passive"))
    )
    (net (code "52") (name "Net-(D9-Pad2)") (class "Default")
      (node (ref "D9") (pin "2") (pinfunction "2_2") (pintype "passive"))
      (node (ref "J3") (pin "1") (pinfunction "1_1") (pintype "passive"))
      (node (ref "R46") (pin "2") (pinfunction "2_2") (pintype "passive"))
    )
    (net (code "53") (name "Net-(LED1-A-Pad3)") (class "Default")
      (node (ref "LED1") (pin "3") (pinfunction "A_3") (pintype "passive"))
      (node (ref "LED1") (pin "4") (pinfunction "A_4") (pintype "passive"))
      (node (ref "R23") (pin "2") (pinfunction "2_2") (pintype "passive"))
    )
    (net (code "54") (name "Net-(LED2-A)") (class "Default")
      (node (ref "LED2") (pin "1") (pinfunction "A_1") (pintype "passive"))
      (node (ref "R44") (pin "2") (pinfunction "2_2") (pintype "passive"))
    )
    (net (code "55") (name "Net-(LED3-A)") (class "Default")
      (node (ref "LED3") (pin "1") (pinfunction "A_1") (pintype "passive"))
      (node (ref "LED4") (pin "1") (pinfunction "A_1") (pintype "passive"))
      (node (ref "LED5") (pin "1") (pinfunction "A_1") (pintype "passive"))
      (node (ref "R45") (pin "2") (pinfunction "2_2") (pintype "passive"))
    )
    (net (code "56") (name "Net-(LED6-+)") (class "Default")
      (node (ref "LED6") (pin "2") (pinfunction "+_2") (pintype "passive"))
      (node (ref "R48") (pin "2") (pinfunction "2_2") (pintype "passive"))
    )
    (net (code "57") (name "Net-(Q2-G1)") (class "Default")
      (node (ref "Q2") (pin "2") (pinfunction "G1_2") (pintype "passive"))
      (node (ref "Q2") (pin "4") (pinfunction "G2_4") (pintype "passive"))
      (node (ref "R24") (pin "2") (pinfunction "2_2") (pintype "passive"))
      (node (ref "R25") (pin "2") (pinfunction "2_2") (pintype "passive"))
    )
    (net (code "58") (name "Net-(Q3-G)") (class "Default")
      (node (ref "Q3") (pin "1") (pinfunction "G_1") (pintype "passive"))
      (node (ref "Q6") (pin "2") (pinfunction "E_2") (pintype "passive"))
      (node (ref "R32") (pin "1") (pintype "passive"))
    )
    (net (code "59") (name "Net-(Q3-S)") (class "Default")
      (node (ref "Q3") (pin "3") (pinfunction "S_3") (pintype "passive"))
      (node (ref "R35") (pin "2") (pinfunction "2_2") (pintype "passive"))
      (node (ref "R39") (pin "2") (pinfunction "2_2") (pintype "passive"))
    )
    (net (code "60") (name "Net-(Q4-B)") (class "Default")
      (node (ref "Q4") (pin "1") (pinfunction "B_1") (pintype "passive"))
      (node (ref "R26") (pin "1") (pinfunction "1_1") (pintype "passive"))
      (node (ref "R28") (pin "2") (pinfunction "2_2") (pintype "passive"))
    )
    (net (code "61") (name "Net-(Q5-B)") (class "Default")
      (node (ref "Q5") (pin "1") (pinfunction "B_1") (pintype "passive"))
      (node (ref "R31") (pin "2") (pinfunction "2_2") (pintype "passive"))
      (node (ref "R36") (pin "2") (pinfunction "2_2") (pintype "passive"))
    )
    (net (code "62") (name "Net-(Q5-C)") (class "Default")
      (node (ref "Q5") (pin "3") (pinfunction "C_3") (pintype "passive"))
      (node (ref "R28") (pin "1") (pinfunction "1_1") (pintype "passive"))
    )
    (net (code "63") (name "Net-(R27-Pad2)") (class "Default")
      (node (ref "R27") (pin "2") (pinfunction "2_2") (pintype "passive"))
      (node (ref "R30") (pin "1") (pinfunction "1_1") (pintype "passive"))
      (node (ref "R34") (pin "1") (pinfunction "1_1") (pintype "passive"))
    )
    (net (code "64") (name "Net-(U5-ICHAG)") (class "Default")
      (node (ref "R22") (pin "1") (pinfunction "1_1") (pintype "passive"))
      (node (ref "U5") (pin "6") (pinfunction "ICHAG_6") (pintype "passive"))
    )
    (net (code "65") (name "Net-(U5-LX)") (class "Default")
      (node (ref "FB2") (pin "1") (pinfunction "1_1") (pintype "passive"))
      (node (ref "U5") (pin "3") (pinfunction "LX_3") (pintype "passive"))
    )
    (net (code "66") (name "Net-(U6-C2)") (class "Default")
      (node (ref "R29") (pin "2") (pinfunction "2_2") (pintype "passive"))
      (node (ref "U6") (pin "8") (pinfunction "C2_8") (pintype "passive"))
    )
    (net (code "67") (name "Net-(U7-PF2-NRST)") (class "Default")
      (node (ref "C48") (pin "2") (pintype "passive"))
      (node (ref "R41") (pin "2") (pinfunction "2_2") (pintype "passive"))
      (node (ref "U7") (pin "3") (pinfunction "PF2-NRST_3") (pintype "passive"))
    )
    (net (code "68") (name "Net-(U7-PF8-BOOT0)") (class "Default")
      (node (ref "R43") (pin "1") (pinfunction "1_1") (pintype "passive"))
      (node (ref "U7") (pin "30") (pinfunction "PF8-BOOT0_30") (pintype "passive"))
    )
    (net (code "69") (name "VCC_USB") (class "Default")
      (node (ref "C27") (pin "1") (pinfunction "1_1") (pintype "passive"))
      (node (ref "C29") (pin "1") (pintype "passive"))
      (node (ref "C49") (pin "2") (pintype "passive"))
      (node (ref "L4") (pin "1") (pinfunction "1_1") (pintype "passive"))
      (node (ref "U5") (pin "1") (pinfunction "VIN_1") (pintype "passive"))
    )
    (net (code "70") (name "unconnected-(P3-Pad4)") (class "Default")
      (node (ref "P3") (pin "4") (pinfunction "4_4") (pintype "passive"))
    )
    (net (code "71") (name "unconnected-(U6-Pad21)") (class "Default")
      (node (ref "U6") (pin "21") (pinfunction "21_21") (pintype "passive"))
    )
    (net (code "72") (name "unconnected-(U7-PA0-Pad6)") (class "Default")
      (node (ref "U7") (pin "6") (pinfunction "PA0_6") (pintype "passive"))
    )
    (net (code "73") (name "unconnected-(U7-PA6-Pad12)") (class "Default")
      (node (ref "U7") (pin "12") (pinfunction "PA6_12") (pintype "passive"))
    )
  )
)
